# IoT_Greenhouse_V1_0_A_-_Pwr_Input.net
KiCad netlist of a schematic drawn in Altium Designer
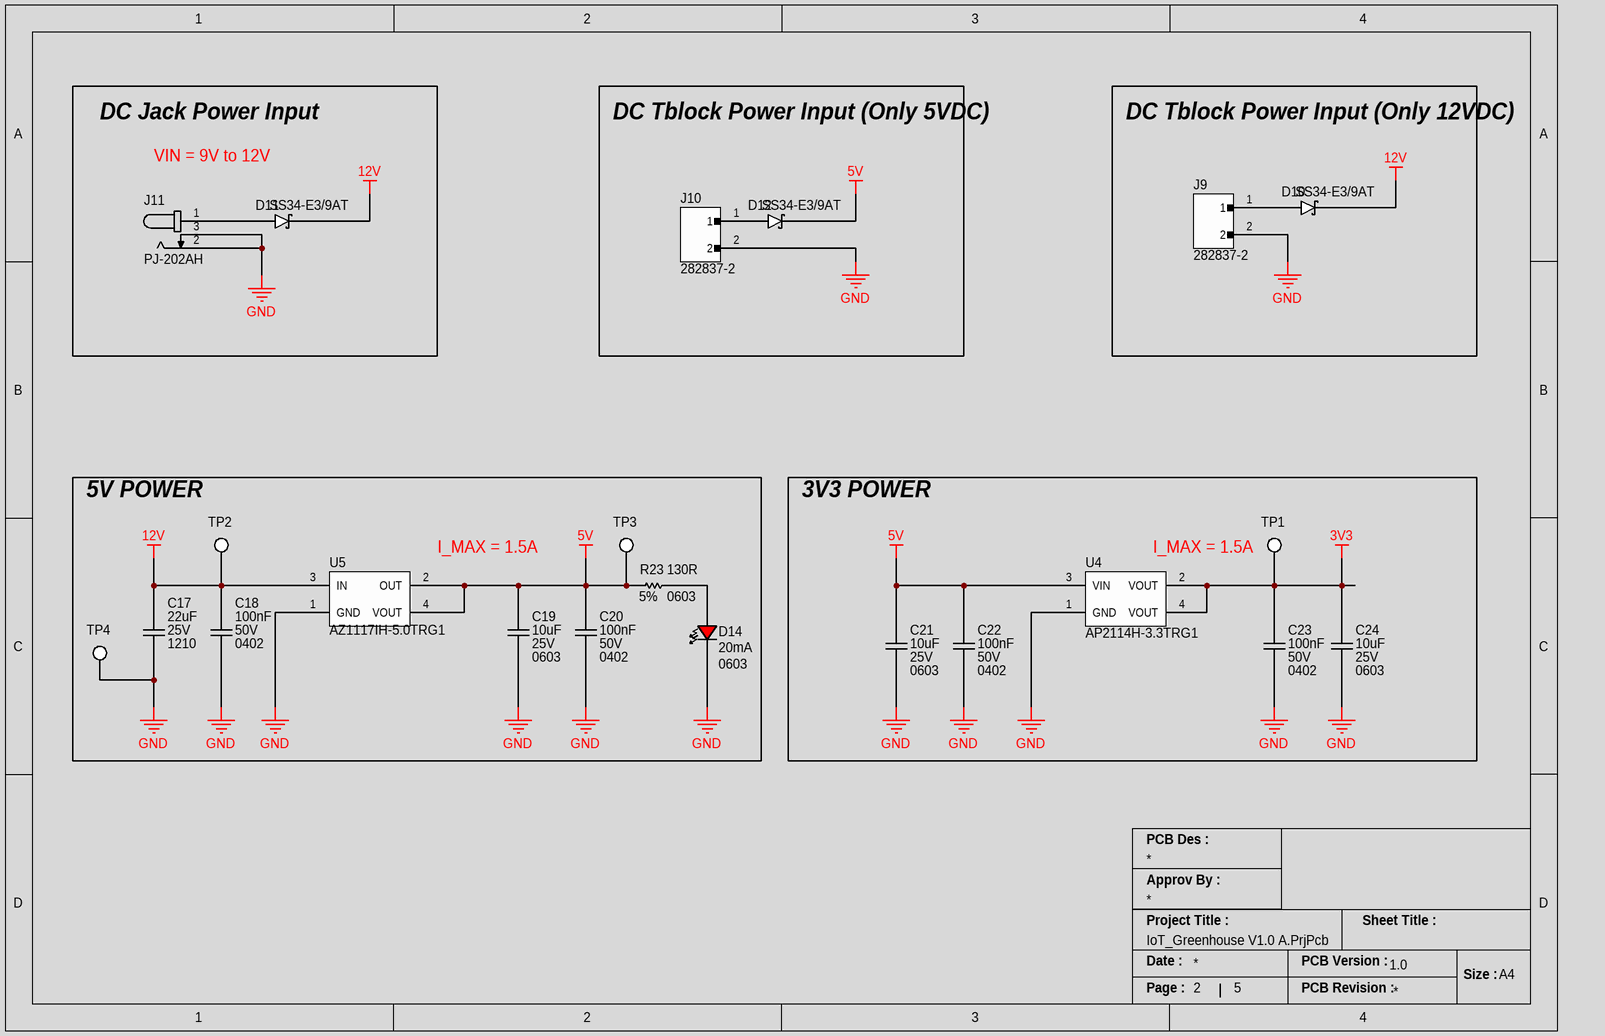
[diagram p0: IoT_Greenhouse V1.0 A - Pwr Input.SchDoc]

(export (version "E")
  (design (tool "Eeschema 10.0.6"))
  (components
    (comp (ref "C17")
      (value "GRM32ER71E226KE15L")
      (footprint "CAP_1210_CAPC3225X270N")
      (description "Multilayer Ceramic Capacitor, 22 uF, 25 V, ± 10%, X7R, 1210 [3225 Metric]")
      (fields
        (field (name "MANUFACTURER") "Murata")
        (field (name "TOLERANCE") "10%")
        (field (name "VOLTAGE RATING") "25V")
        (field (name "CAPACITANCE") "22uF")
        (field (name "CASE/PACKAGE") "1210")
      )
      (libsource (lib "Electronic Devices_LIB") (part "CAP_22UF_25V_X7R_1210"))
    )
    (comp (ref "C18")
      (value "GRM155R71H104KE14D")
      (footprint "CAP_0402_CAPC1005X05N")
      (description "Multilayer Ceramic Capacitor, 0.1 uF, 16 V, ± 10%, X7R, 0402 [1005 Metric]")
      (fields
        (field (name "MANUFACTURER") "Murata")
        (field (name "TOLERANCE") "10%")
        (field (name "VOLTAGE RATING") "50V")
        (field (name "CAPACITANCE") "100nF")
        (field (name "CASE/PACKAGE") "0402")
      )
      (libsource (lib "Electronic Devices_LIB") (part "CAP_100NF_50V_X7R_0402"))
    )
    (comp (ref "C19")
      (value "GRM188R61E106MA73D")
      (footprint "CAP_0603_CAPC1608X08N")
      (description "Multilayer Ceramic Capacitor, 10 uF, 25 V, ± 20%, X5R, 0603 [1608 Metric]")
      (fields
        (field (name "MANUFACTURER") "Murata")
        (field (name "TOLERANCE") "20%")
        (field (name "CASE/PACKAGE") "0603")
        (field (name "CAPACITANCE") "10uF")
        (field (name "VOLTAGE RATING") "25V")
      )
      (libsource (lib "Electronic Devices_LIB") (part "CAP_10UF_25V_X5R_0603"))
    )
    (comp (ref "C20")
      (value "GRM155R71H104KE14D")
      (footprint "CAP_0402_CAPC1005X05N")
      (description "Multilayer Ceramic Capacitor, 0.1 uF, 16 V, ± 10%, X7R, 0402 [1005 Metric]")
      (fields
        (field (name "MANUFACTURER") "Murata")
        (field (name "TOLERANCE") "10%")
        (field (name "VOLTAGE RATING") "50V")
        (field (name "CAPACITANCE") "100nF")
        (field (name "CASE/PACKAGE") "0402")
      )
      (libsource (lib "Electronic Devices_LIB") (part "CAP_100NF_50V_X7R_0402"))
    )
    (comp (ref "C21")
      (value "GRM188R61E106MA73D")
      (footprint "CAP_0603_CAPC1608X08N")
      (description "Multilayer Ceramic Capacitor, 10 uF, 25 V, ± 20%, X5R, 0603 [1608 Metric]")
      (fields
        (field (name "MANUFACTURER") "Murata")
        (field (name "TOLERANCE") "20%")
        (field (name "CASE/PACKAGE") "0603")
        (field (name "CAPACITANCE") "10uF")
        (field (name "VOLTAGE RATING") "25V")
      )
      (libsource (lib "Electronic Devices_LIB") (part "CAP_10UF_25V_X5R_0603"))
    )
    (comp (ref "C22")
      (value "GRM155R71H104KE14D")
      (footprint "CAP_0402_CAPC1005X05N")
      (description "Multilayer Ceramic Capacitor, 0.1 uF, 16 V, ± 10%, X7R, 0402 [1005 Metric]")
      (fields
        (field (name "MANUFACTURER") "Murata")
        (field (name "TOLERANCE") "10%")
        (field (name "VOLTAGE RATING") "50V")
        (field (name "CAPACITANCE") "100nF")
        (field (name "CASE/PACKAGE") "0402")
      )
      (libsource (lib "Electronic Devices_LIB") (part "CAP_100NF_50V_X7R_0402"))
    )
    (comp (ref "C23")
      (value "GRM155R71H104KE14D")
      (footprint "CAP_0402_CAPC1005X05N")
      (description "Multilayer Ceramic Capacitor, 0.1 uF, 16 V, ± 10%, X7R, 0402 [1005 Metric]")
      (fields
        (field (name "MANUFACTURER") "Murata")
        (field (name "TOLERANCE") "10%")
        (field (name "VOLTAGE RATING") "50V")
        (field (name "CAPACITANCE") "100nF")
        (field (name "CASE/PACKAGE") "0402")
      )
      (libsource (lib "Electronic Devices_LIB") (part "CAP_100NF_50V_X7R_0402"))
    )
    (comp (ref "C24")
      (value "GRM188R61E106MA73D")
      (footprint "CAP_0603_CAPC1608X08N")
      (description "Multilayer Ceramic Capacitor, 10 uF, 25 V, ± 20%, X5R, 0603 [1608 Metric]")
      (fields
        (field (name "MANUFACTURER") "Murata")
        (field (name "TOLERANCE") "20%")
        (field (name "CASE/PACKAGE") "0603")
        (field (name "CAPACITANCE") "10uF")
        (field (name "VOLTAGE RATING") "25V")
      )
      (libsource (lib "Electronic Devices_LIB") (part "CAP_10UF_25V_X5R_0603"))
    )
    (comp (ref "D10")
      (value "SS34-E3/9AT")
      (footprint "DIO_Vishay_SMC_MFG")
      (description "Rectifier Diode, schottky, 40V V(Rrm), do-214Ab / Smc")
      (fields (field (name "MANUFACTURER") "Vishay Semiconductors"))
      (libsource (lib "Electronic Devices_LIB") (part "DIO_SCTKY_40V_3A"))
    )
    (comp (ref "D11")
      (value "SS34-E3/9AT")
      (footprint "DIO_Vishay_SMC_MFG")
      (description "Rectifier Diode, schottky, 40V V(Rrm), do-214Ab / Smc")
      (fields (field (name "MANUFACTURER") "Vishay Semiconductors"))
      (libsource (lib "Electronic Devices_LIB") (part "DIO_SCTKY_40V_3A"))
    )
    (comp (ref "D12")
      (value "SS34-E3/9AT")
      (footprint "DIO_Vishay_SMC_MFG")
      (description "Rectifier Diode, schottky, 40V V(Rrm), do-214Ab / Smc")
      (fields (field (name "MANUFACTURER") "Vishay Semiconductors"))
      (libsource (lib "Electronic Devices_LIB") (part "DIO_SCTKY_40V_3A"))
    )
    (comp (ref "D14")
      (value "LTST-C190KRKT")
      (footprint "LED_0603-RED-0.75mm")
      (description "LED,  LTST-C190KRKT")
      (fields
        (field (name "MANUFACTURER") "Vishay Lite-On")
        (field (name "TEST CURRENT") "20mA")
        (field (name "CASE/PACKAGE") "0603")
      )
      (libsource (lib "Electronic Devices_LIB") (part "LED_DIO_RED_20mA_0603"))
    )
    (comp (ref "J9")
      (value "282837-2")
      (footprint "CONN_TBLOCK_2P_{backslash}2828372")
      (description "Connector, Terminal Block; Wire Receptacle; 2 Pos.; 16-30 AWG; 0.2 in. CL; Side;")
      (fields (field (name "MANUFACTURER") "TE Connectivity") (field (name "VOLTAGE") "300V"))
      (libsource (lib "Electronic Devices_LIB") (part "CONN_TBLOCK_2P_5.08mm_282837-2"))
    )
    (comp (ref "J10")
      (value "282837-2")
      (footprint "CONN_TBLOCK_2P_{backslash}2828372")
      (description "Connector, Terminal Block; Wire Receptacle; 2 Pos.; 16-30 AWG; 0.2 in. CL; Side;")
      (fields (field (name "MANUFACTURER") "TE Connectivity") (field (name "VOLTAGE") "300V"))
      (libsource (lib "Electronic Devices_LIB") (part "CONN_TBLOCK_2P_5.08mm_282837-2"))
    )
    (comp (ref "J11")
      (value "PJ-202AH")
      (footprint "CONN_CUI_PJ-202AH")
      (description "2.0 x 6.5 mm, 5.0 A, Horizontal, Through Hole, Kinked Pins, Dc Power Jack Connector")
      (fields (field (name "MANUFACTURER") "CUI Devices"))
      (libsource (lib "Electronic Devices_LIB") (part "CONN_DC_JACK_2X6.5mm_PJ-202AH"))
    )
    (comp (ref "R23")
      (value "RC0603JR-07130RL")
      (footprint "RES_0603_RESC1608X04N")
      (description "Res Thick Film 0603 130 Ohm 5% 1/10W ±100ppm/°C Molded SMD SMD Paper T/R")
      (fields
        (field (name "MANUFACTURER") "Yageo")
        (field (name "TOLERANCE") "5%")
        (field (name "RESISTENCE") "130R")
        (field (name "CASE/PACKCAGE") "0603")
      )
      (libsource (lib "Electronic Devices_LIB") (part "RES_130R_5%_100mW_0603"))
    )
    (comp (ref "TP1")
      (value "NO COMPONENT")
      (footprint "TP_PAD_1.6MM_SMD_ROUND")
      (description "Test Point, SMD pad, round, 1.5mm, 1.6mm, 3mm diameter")
      (libsource (lib "Electronic Devices_LIB") (part "TP_PAD_SMD_Round"))
    )
    (comp (ref "TP2")
      (value "NO COMPONENT")
      (footprint "TP_PAD_1.6MM_SMD_ROUND")
      (description "Test Point, SMD pad, round, 1.5mm, 1.6mm, 3mm diameter")
      (libsource (lib "Electronic Devices_LIB") (part "TP_PAD_SMD_Round"))
    )
    (comp (ref "TP3")
      (value "NO COMPONENT")
      (footprint "TP_PAD_1.6MM_SMD_ROUND")
      (description "Test Point, SMD pad, round, 1.5mm, 1.6mm, 3mm diameter")
      (libsource (lib "Electronic Devices_LIB") (part "TP_PAD_SMD_Round"))
    )
    (comp (ref "TP4")
      (value "NO COMPONENT")
      (footprint "TP_PAD_1.6MM_SMD_ROUND")
      (description "Test Point, SMD pad, round, 1.5mm, 1.6mm, 3mm diameter")
      (libsource (lib "Electronic Devices_LIB") (part "TP_PAD_SMD_Round"))
    )
    (comp (ref "U4")
      (value "AP2114H-3.3TRG1")
      (footprint "IC_REG_SOT230P700X180-4N")
      (description "IC REG LDO 3.3V 1A SOT223")
      (fields (field (name "MANUFACTURER") "Diodes"))
      (libsource (lib "Electronic Devices_LIB") (part "IC_REG_LDO_3.3V_1A_AP2114H-3.3TRG1"))
    )
    (comp (ref "U5")
      (value "AZ1117IH-5.0TRG1")
      (footprint "IC_REG_SOT230P700X180-4N")
      (description "LDO Regulator Pos 5V 1A 3-Pin SOT-223 T/R")
      (fields (field (name "MANUFACTURER") "Diodes"))
      (libsource (lib "Electronic Devices_LIB") (part "IC_REG_LDO_5V_1A_AZ1117IH-5.0TRG1"))
    )
  )
  (nets
    (net (code "1") (name "3V3") (class "Default")
      (node (ref "C23") (pin "2") (pinfunction "2_2") (pintype "passive"))
      (node (ref "C24") (pin "2") (pinfunction "2_2") (pintype "passive"))
      (node (ref "TP1") (pin "1") (pinfunction "1_1") (pintype "passive"))
      (node (ref "U4") (pin "2") (pinfunction "VOUT_2") (pintype "passive"))
      (node (ref "U4") (pin "4") (pinfunction "VOUT_4") (pintype "passive"))
    )
    (net (code "2") (name "5V") (class "Default")
      (node (ref "C19") (pin "2") (pinfunction "2_2") (pintype "passive"))
      (node (ref "C20") (pin "2") (pinfunction "2_2") (pintype "passive"))
      (node (ref "C21") (pin "2") (pinfunction "2_2") (pintype "passive"))
      (node (ref "C22") (pin "2") (pinfunction "2_2") (pintype "passive"))
      (node (ref "D12") (pin "1") (pinfunction "K_1") (pintype "passive"))
      (node (ref "R23") (pin "1") (pinfunction "1_1") (pintype "passive"))
      (node (ref "TP3") (pin "1") (pinfunction "1_1") (pintype "passive"))
      (node (ref "U4") (pin "3") (pinfunction "VIN_3") (pintype "passive"))
      (node (ref "U5") (pin "2") (pinfunction "OUT_2") (pintype "passive"))
      (node (ref "U5") (pin "4") (pinfunction "VOUT_4") (pintype "passive"))
    )
    (net (code "3") (name "12V") (class "Default")
      (node (ref "C17") (pin "2") (pinfunction "2_2") (pintype "passive"))
      (node (ref "C18") (pin "2") (pinfunction "2_2") (pintype "passive"))
      (node (ref "D10") (pin "1") (pinfunction "K_1") (pintype "passive"))
      (node (ref "D11") (pin "1") (pinfunction "K_1") (pintype "passive"))
      (node (ref "TP2") (pin "1") (pinfunction "1_1") (pintype "passive"))
      (node (ref "U5") (pin "3") (pinfunction "IN_3") (pintype "passive"))
    )
    (net (code "4") (name "GND") (class "Default")
      (node (ref "C17") (pin "1") (pinfunction "1_1") (pintype "passive"))
      (node (ref "C18") (pin "1") (pinfunction "1_1") (pintype "passive"))
      (node (ref "C19") (pin "1") (pinfunction "1_1") (pintype "passive"))
      (node (ref "C20") (pin "1") (pinfunction "1_1") (pintype "passive"))
      (node (ref "C21") (pin "1") (pinfunction "1_1") (pintype "passive"))
      (node (ref "C22") (pin "1") (pinfunction "1_1") (pintype "passive"))
      (node (ref "C23") (pin "1") (pinfunction "1_1") (pintype "passive"))
      (node (ref "C24") (pin "1") (pinfunction "1_1") (pintype "passive"))
      (node (ref "D14") (pin "1") (pinfunction "C_1") (pintype "passive"))
      (node (ref "J10") (pin "2") (pinfunction "2_2") (pintype "passive"))
      (node (ref "J11") (pin "2") (pinfunction "2_2") (pintype "passive"))
      (node (ref "J11") (pin "3") (pinfunction "3_3") (pintype "passive"))
      (node (ref "J9") (pin "2") (pinfunction "2_2") (pintype "passive"))
      (node (ref "TP4") (pin "1") (pinfunction "1_1") (pintype "passive"))
      (node (ref "U4") (pin "1") (pinfunction "GND_1") (pintype "passive"))
      (node (ref "U5") (pin "1") (pinfunction "GND_1") (pintype "passive"))
    )
    (net (code "5") (name "Net-(D10-A)") (class "Default")
      (node (ref "D10") (pin "2") (pinfunction "A_2") (pintype "passive"))
      (node (ref "J9") (pin "1") (pinfunction "1_1") (pintype "passive"))
    )
    (net (code "6") (name "Net-(D11-A)") (class "Default")
      (node (ref "D11") (pin "2") (pinfunction "A_2") (pintype "passive"))
      (node (ref "J11") (pin "1") (pinfunction "1_1") (pintype "passive"))
    )
    (net (code "7") (name "Net-(D12-A)") (class "Default")
      (node (ref "D12") (pin "2") (pinfunction "A_2") (pintype "passive"))
      (node (ref "J10") (pin "1") (pinfunction "1_1") (pintype "passive"))
    )
    (net (code "8") (name "Net-(D14-A)") (class "Default")
      (node (ref "D14") (pin "2") (pinfunction "A_2") (pintype "passive"))
      (node (ref "R23") (pin "2") (pinfunction "2_2") (pintype "passive"))
    )
  )
)
